# MotorBoardDev.net
KiCad netlist of a schematic drawn in EAGLE
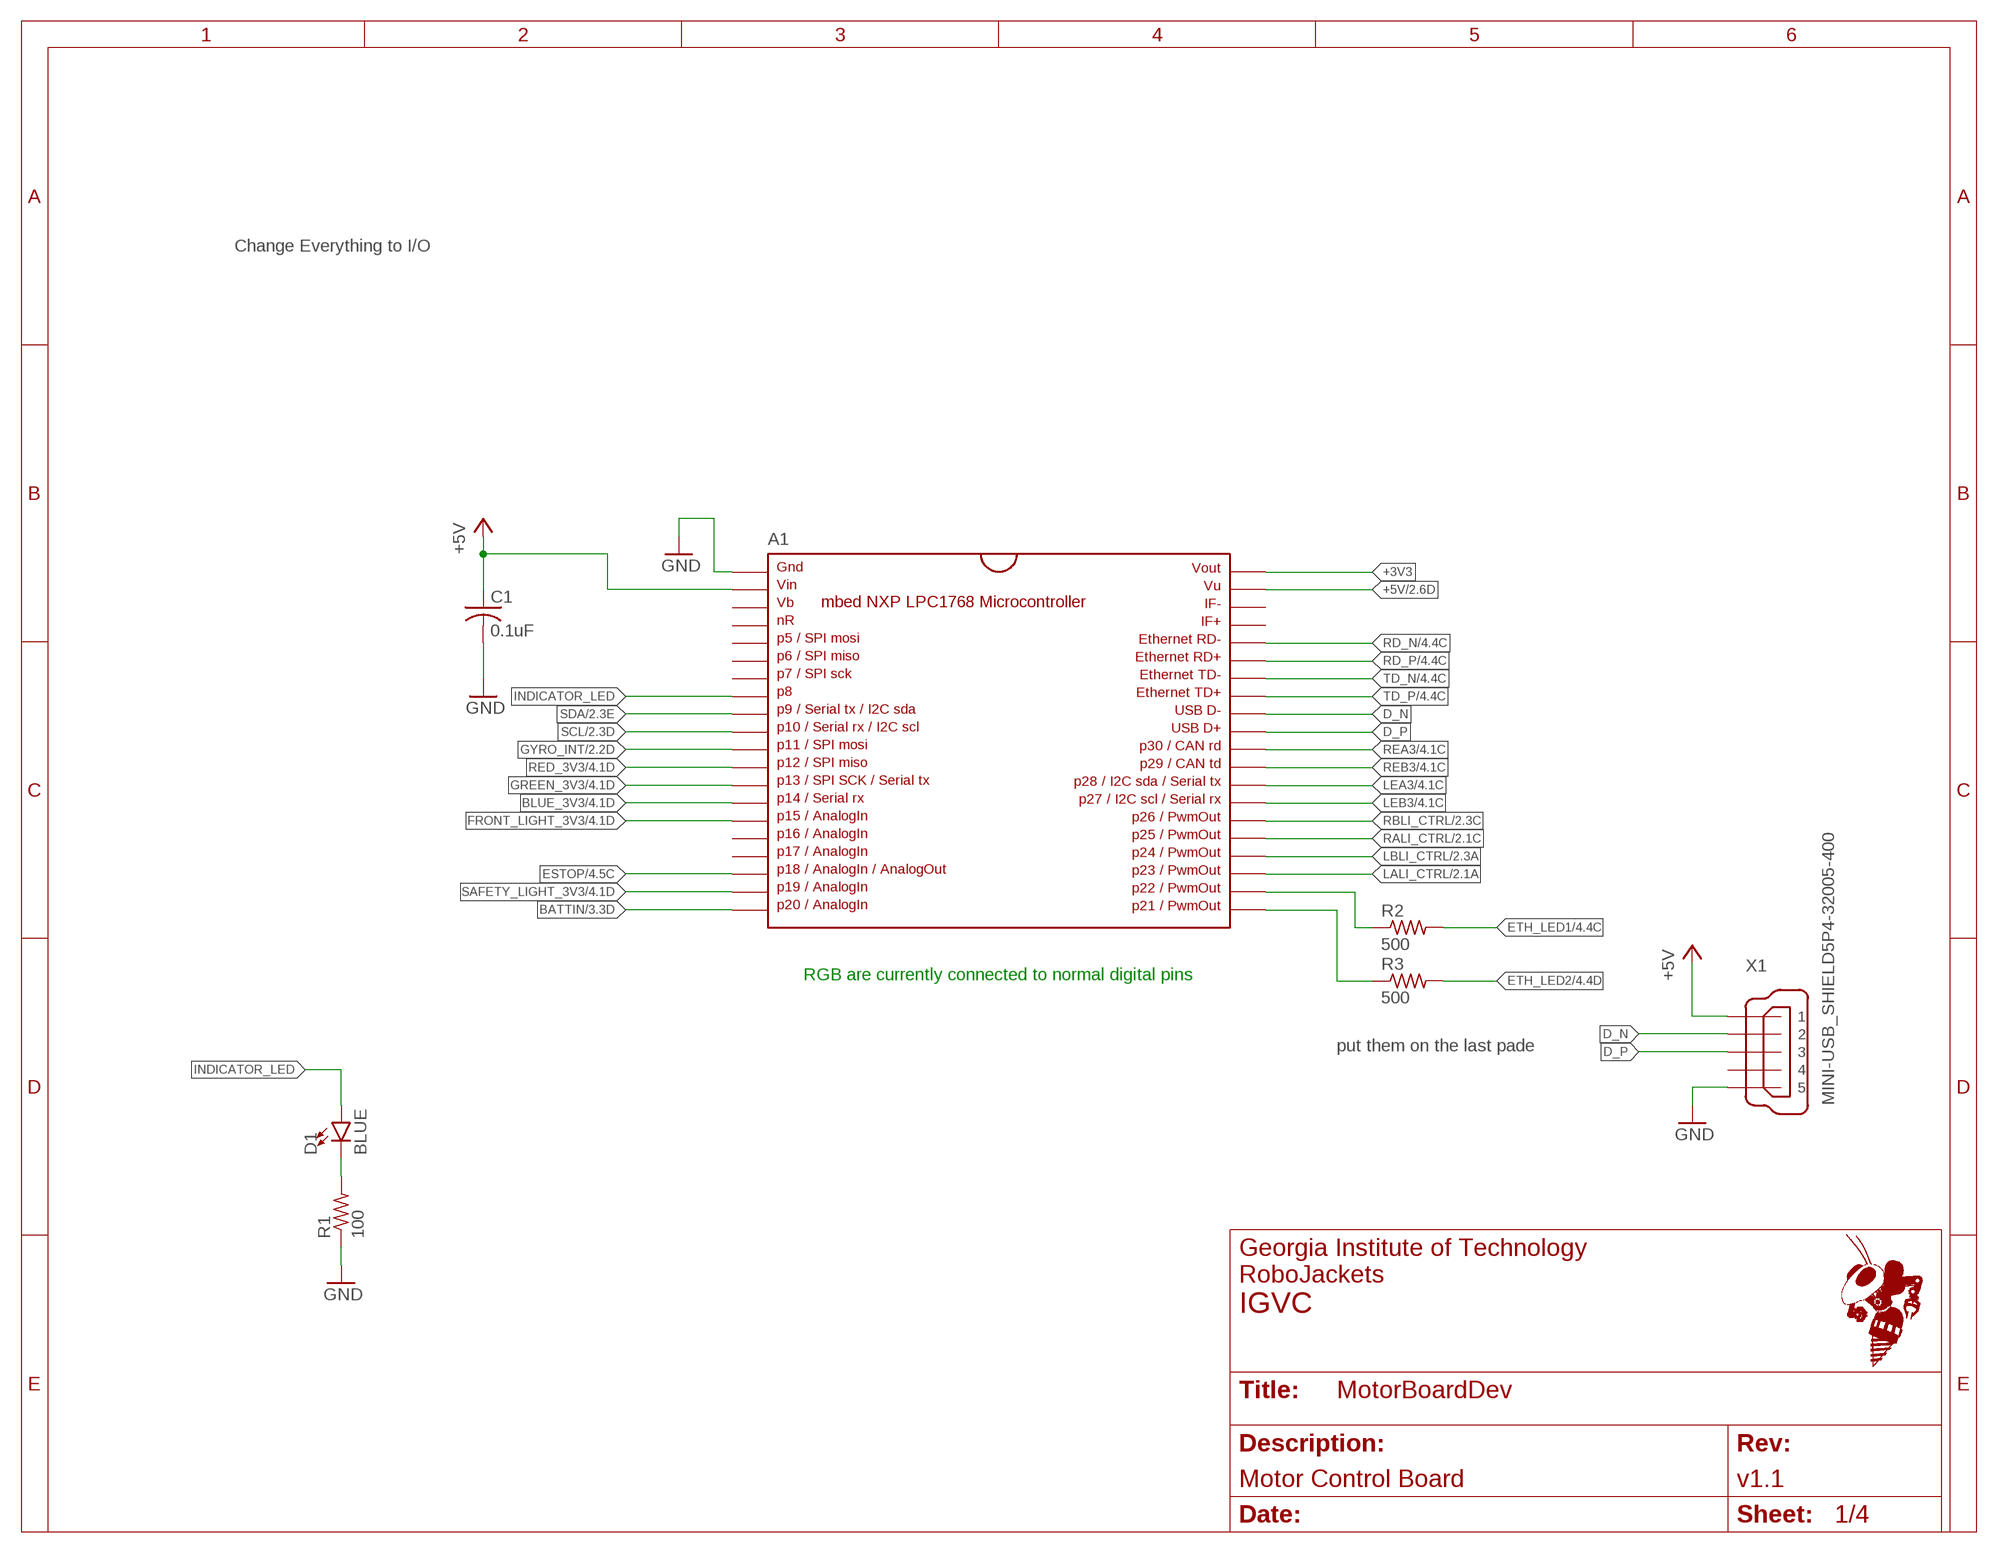
[diagram p0: schematic, sheet 1]
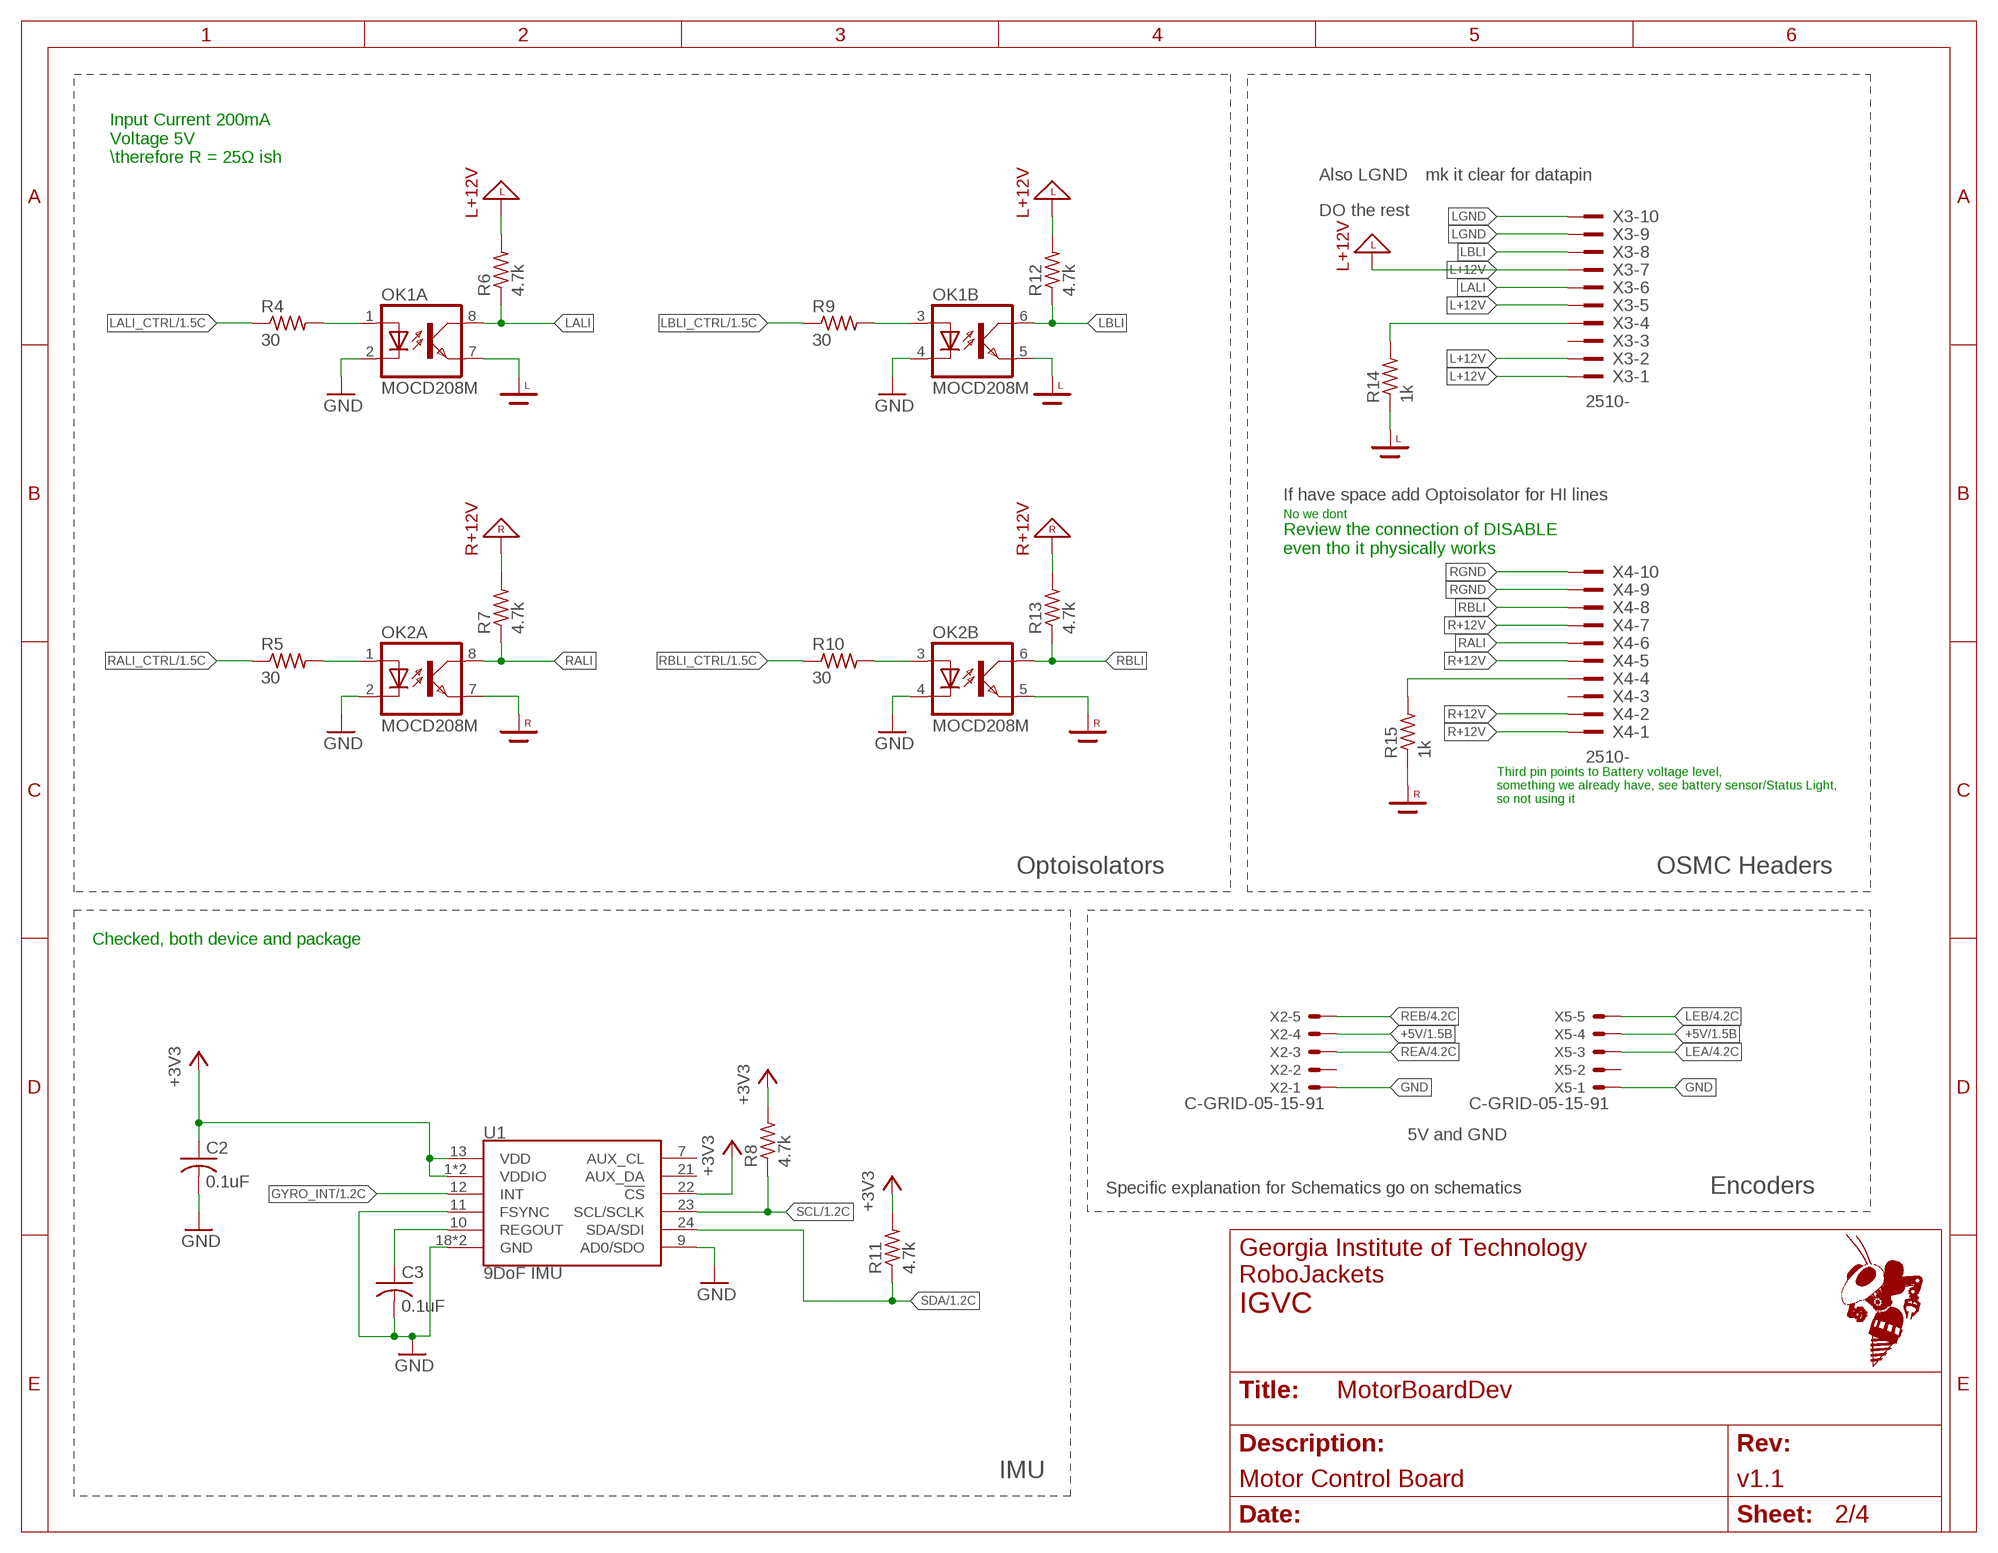
[diagram p1: schematic, sheet 2]
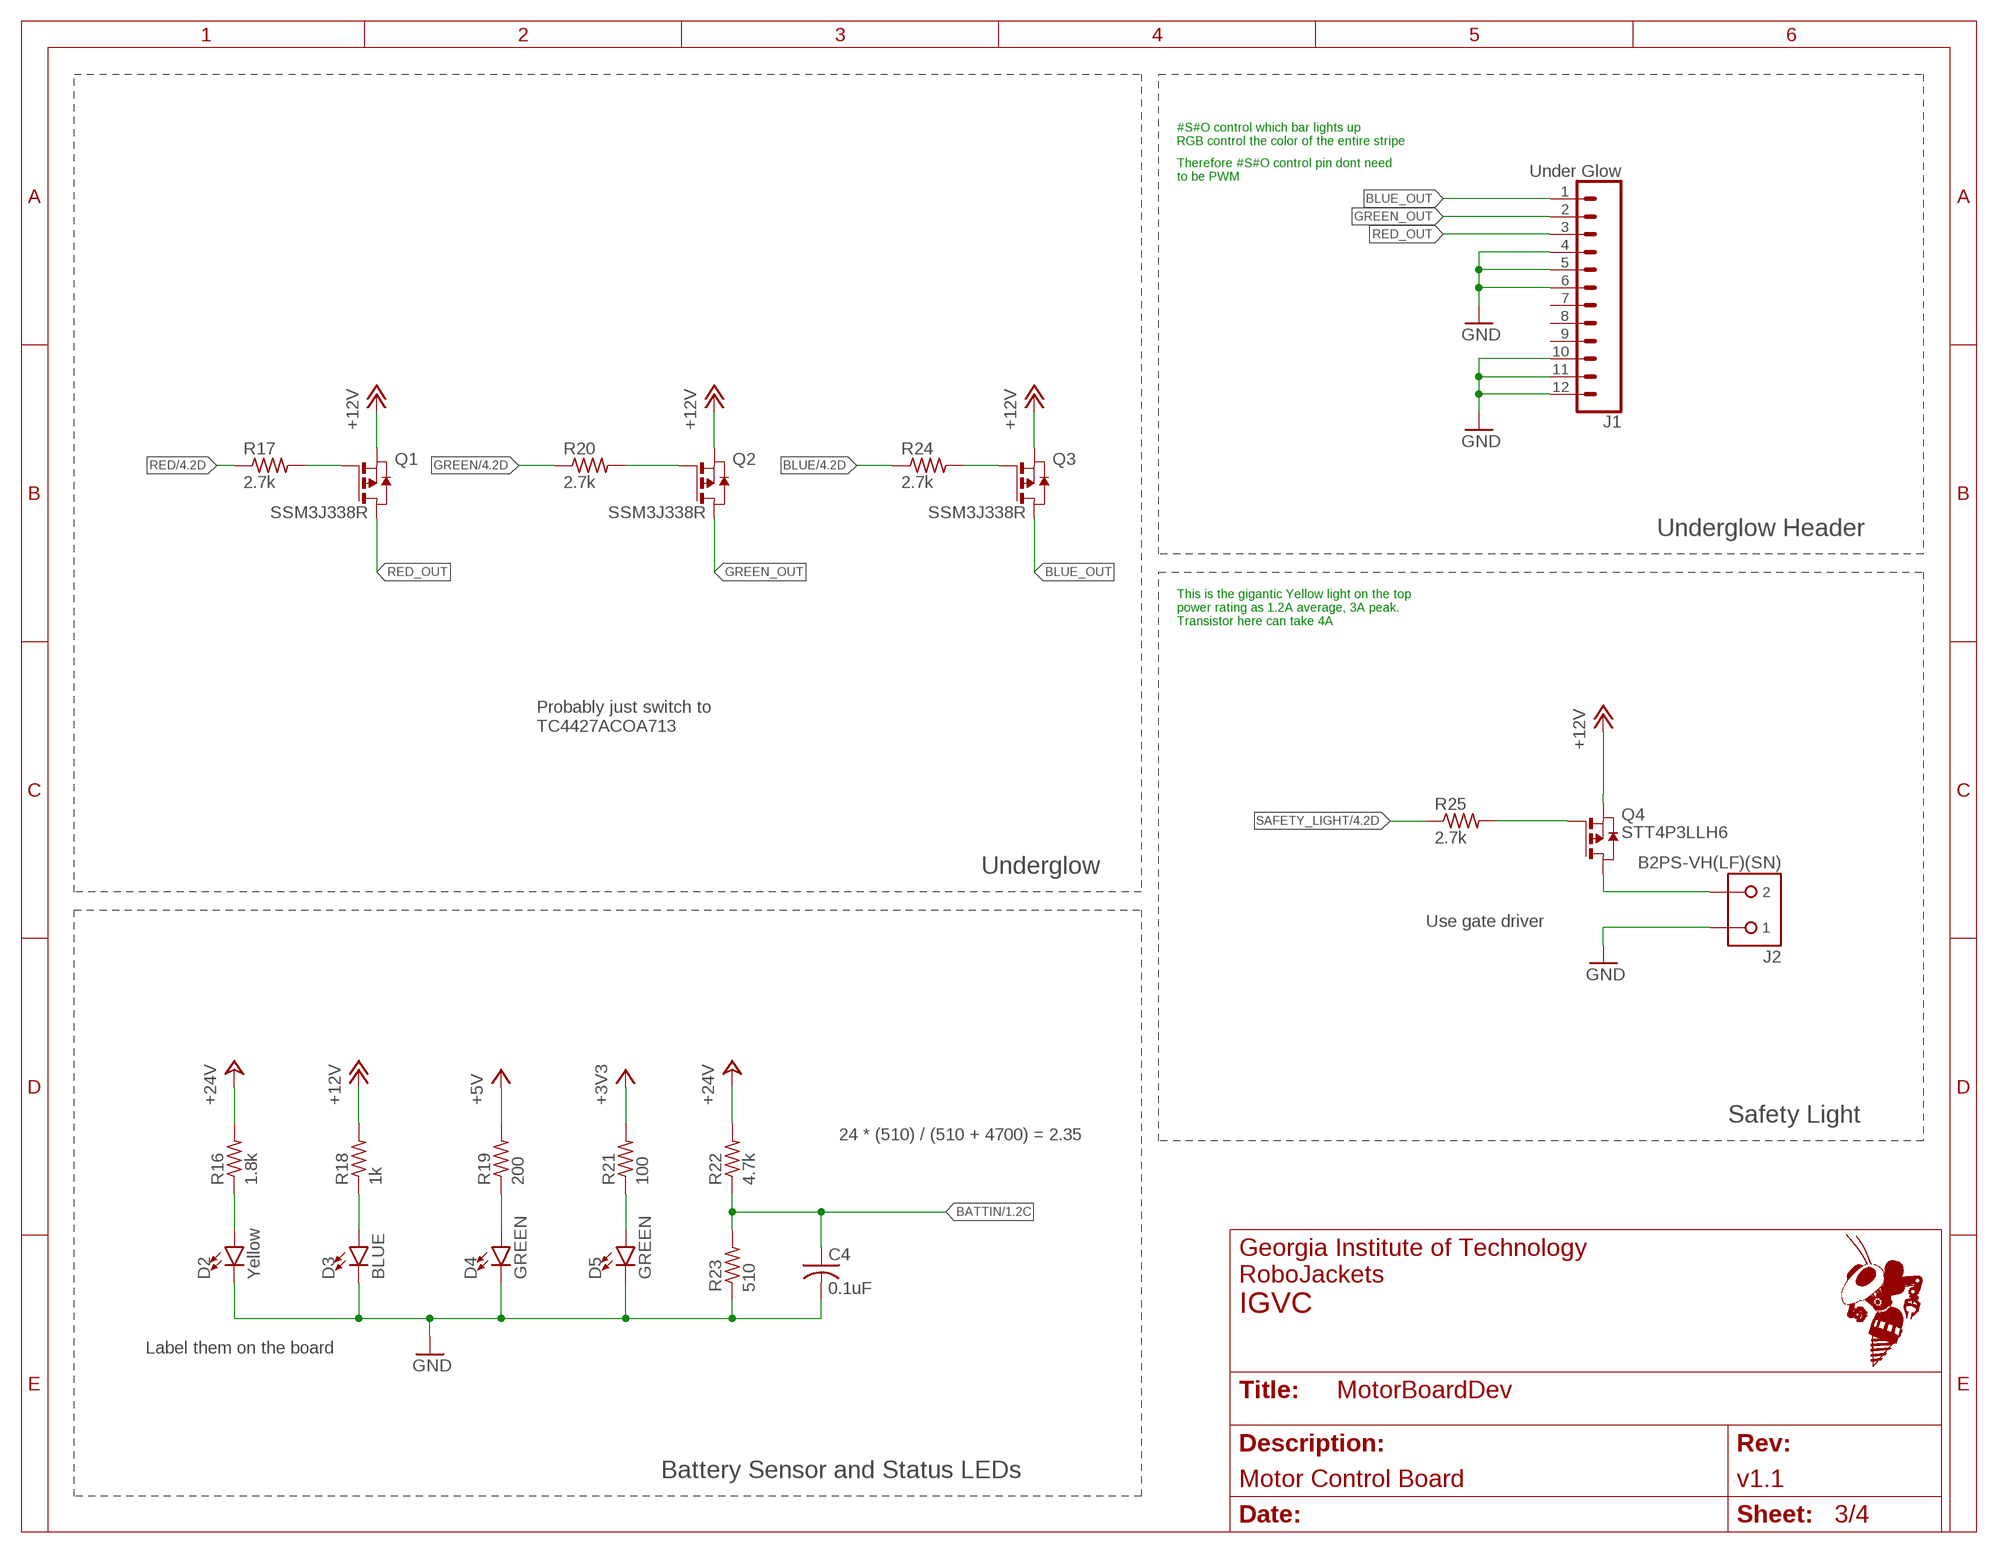
[diagram p2: schematic, sheet 3]
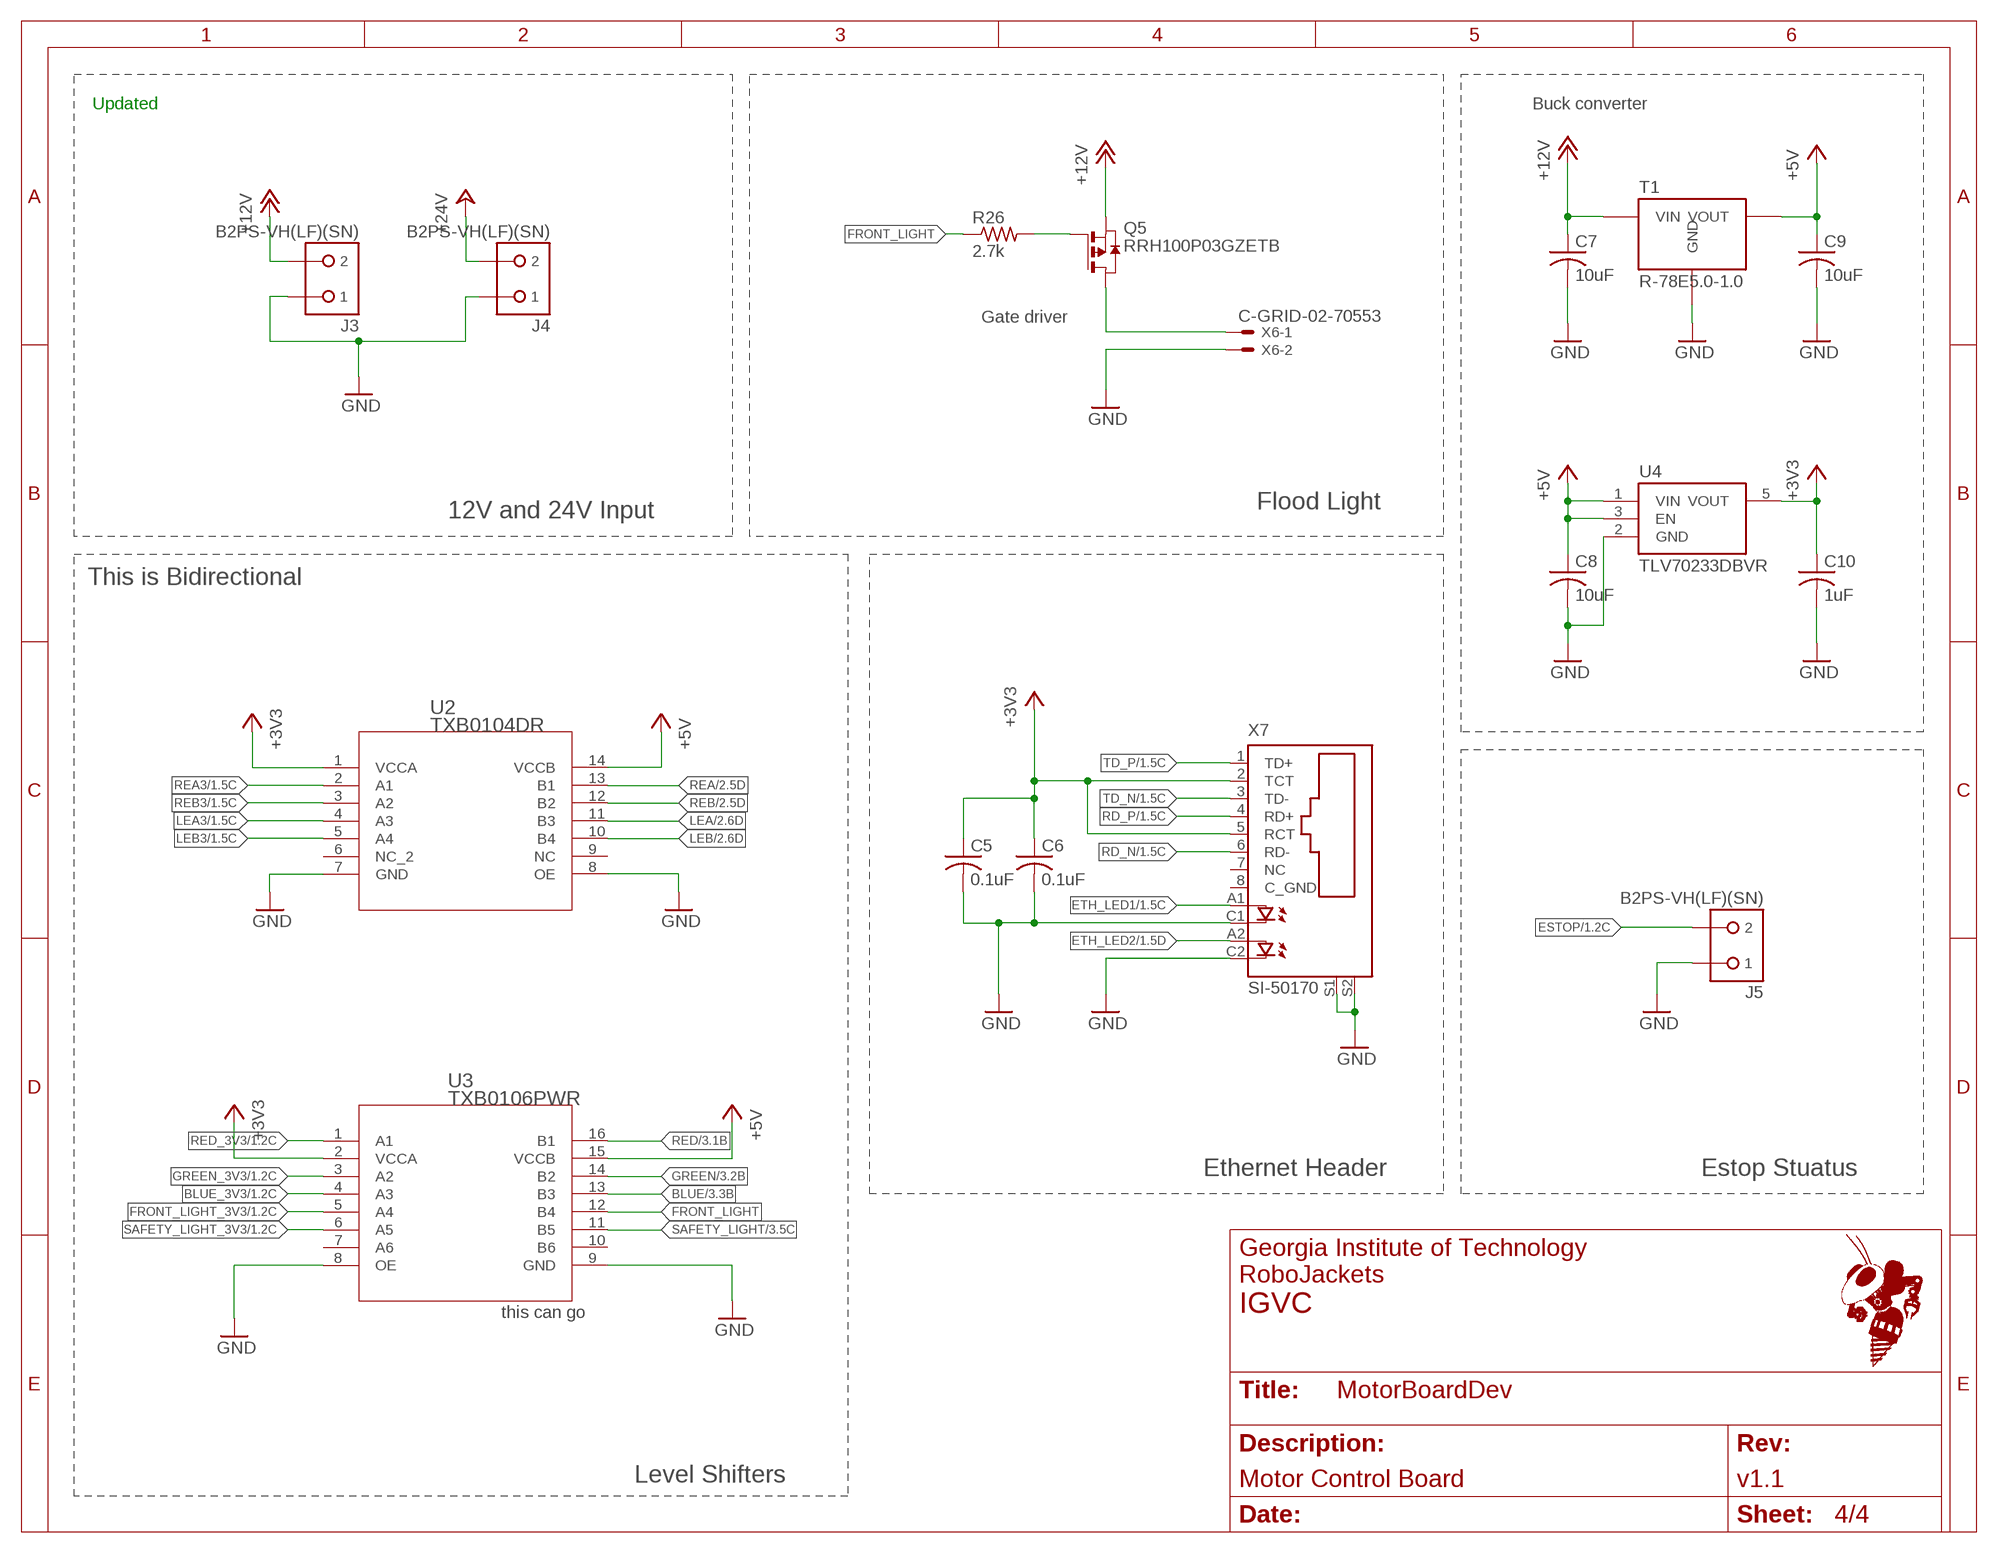
[diagram p3: schematic, sheet 4]

(export (version "E")
  (design (tool "Eeschema 10.0.6"))
  (components
    (comp (ref "C5")
      (value "0.1uF")
      (footprint "eagle-import:C0603")
      (libsource (lib "eagle-import") (part "C-USC0603"))
    )
    (comp (ref "C6")
      (value "0.1uF")
      (footprint "eagle-import:C0603")
      (libsource (lib "eagle-import") (part "C-USC0603"))
    )
    (comp (ref "C7")
      (value "10uF")
      (footprint "eagle-import:C0805")
      (libsource (lib "eagle-import") (part "C-USC0805"))
    )
    (comp (ref "C8")
      (value "10uF")
      (footprint "eagle-import:C0805")
      (libsource (lib "eagle-import") (part "C-USC0805"))
    )
    (comp (ref "C9")
      (value "10uF")
      (footprint "eagle-import:C0805")
      (libsource (lib "eagle-import") (part "C-USC0805"))
    )
    (comp (ref "C10")
      (value "1uF")
      (footprint "eagle-import:C0805")
      (libsource (lib "eagle-import") (part "C-USC0805"))
    )
    (comp (ref "J3")
      (value "B2PS-VH(LF)(SN)")
      (footprint "eagle-import:B2PS-CENTERED")
      (libsource (lib "eagle-import") (part "B2P?-VH(LF)(SN)S"))
    )
    (comp (ref "J4")
      (value "B2PS-VH(LF)(SN)")
      (footprint "eagle-import:B2PS-CENTERED")
      (libsource (lib "eagle-import") (part "B2P?-VH(LF)(SN)S"))
    )
    (comp (ref "J5")
      (value "B2PS-VH(LF)(SN)")
      (footprint "eagle-import:B2PS-CENTERED")
      (libsource (lib "eagle-import") (part "B2P?-VH(LF)(SN)S"))
    )
    (comp (ref "Q5")
      (value "RRH100P03GZETB")
      (footprint "eagle-import:SOIC-8")
      (libsource (lib "eagle-import") (part "RRH100P03GZETB"))
    )
    (comp (ref "R26")
      (value "2.7k")
      (footprint "eagle-import:R0603")
      (libsource (lib "eagle-import") (part "R-US_R0603"))
    )
    (comp (ref "T1")
      (value "R-78E5.0-1.0")
      (footprint "eagle-import:R-78E")
      (libsource (lib "eagle-import") (part "R-78E5.0-1.0"))
    )
    (comp (ref "U2")
      (value "TXB0104DR")
      (footprint "eagle-import:D14")
      (libsource (lib "eagle-import") (part "TXB0104DR"))
    )
    (comp (ref "U3")
      (value "TXB0106PWR")
      (footprint "eagle-import:PW16")
      (libsource (lib "eagle-import") (part "TXB0106PWR"))
    )
    (comp (ref "U4")
      (value "TLV70233DBVR")
      (footprint "eagle-import:SOT-23-5")
      (libsource (lib "eagle-import") (part "TLV70233DBVR"))
    )
    (comp (ref "X6")
      (value "C-GRID-02-70553")
      (footprint "eagle-import:70553-02")
      (libsource (lib "eagle-import") (part "C-GRID-02-70553"))
    )
    (comp (ref "X7")
      (value "SI-50170")
      (footprint "eagle-import:SI-50170")
      (libsource (lib "eagle-import") (part "SI-50170"))
    )
    (comp (ref "A1")
      (value "MBED1768")
      (footprint "eagle-import:SPARKFUN-BOARDS_DIL40_0.9")
      (libsource (lib "eagle-import") (part "SPARKFUN-BOARDS_MBED_NXP_LPC1768"))
    )
    (comp (ref "C1")
      (value "0.1uF")
      (footprint "eagle-import:C0603")
      (libsource (lib "eagle-import") (part "C-USC0603"))
    )
    (comp (ref "D1")
      (value "BLUE")
      (footprint "eagle-import:LED-0603")
      (libsource (lib "eagle-import") (part "LED-BLUE0603"))
    )
    (comp (ref "R1")
      (value "100")
      (footprint "eagle-import:R0603")
      (libsource (lib "eagle-import") (part "R-US_R0603"))
    )
    (comp (ref "R2")
      (value "500")
      (footprint "eagle-import:R0603")
      (libsource (lib "eagle-import") (part "R-US_R0603"))
    )
    (comp (ref "R3")
      (value "500")
      (footprint "eagle-import:R0603")
      (libsource (lib "eagle-import") (part "R-US_R0603"))
    )
    (comp (ref "X1")
      (value "MINI-USB_SHIELD5P4-32005-400")
      (footprint "eagle-import:32005-400")
      (libsource (lib "eagle-import") (part "MINI-USB_SHIELD5P4-32005-400"))
    )
    (comp (ref "C2")
      (value "0.1uF")
      (footprint "eagle-import:C0603")
      (libsource (lib "eagle-import") (part "C-USC0603"))
    )
    (comp (ref "C3")
      (value "0.1uF")
      (footprint "eagle-import:C0603")
      (libsource (lib "eagle-import") (part "C-USC0603"))
    )
    (comp (ref "OK1")
      (value "MOCD208M")
      (footprint "eagle-import:SOIC08-FAIRCHILD")
      (fields (field (name "MF") "FAIRCHILD SEMICONDUCTOR"))
      (libsource (lib "eagle-import") (part "MOCD20M8"))
    )
    (comp (ref "OK2")
      (value "MOCD208M")
      (footprint "eagle-import:SOIC08-FAIRCHILD")
      (fields (field (name "MF") "FAIRCHILD SEMICONDUCTOR"))
      (libsource (lib "eagle-import") (part "MOCD20M8"))
    )
    (comp (ref "R4")
      (value "30")
      (footprint "eagle-import:R0603")
      (libsource (lib "eagle-import") (part "R-US_R0603"))
    )
    (comp (ref "R5")
      (value "30")
      (footprint "eagle-import:R0603")
      (libsource (lib "eagle-import") (part "R-US_R0603"))
    )
    (comp (ref "R6")
      (value "4.7k")
      (footprint "eagle-import:R0603")
      (libsource (lib "eagle-import") (part "R-US_R0603"))
    )
    (comp (ref "R7")
      (value "4.7k")
      (footprint "eagle-import:R0603")
      (libsource (lib "eagle-import") (part "R-US_R0603"))
    )
    (comp (ref "R8")
      (value "4.7k")
      (footprint "eagle-import:R0603")
      (libsource (lib "eagle-import") (part "R-US_R0603"))
    )
    (comp (ref "R9")
      (value "30")
      (footprint "eagle-import:R0603")
      (libsource (lib "eagle-import") (part "R-US_R0603"))
    )
    (comp (ref "R10")
      (value "30")
      (footprint "eagle-import:R0603")
      (libsource (lib "eagle-import") (part "R-US_R0603"))
    )
    (comp (ref "R11")
      (value "4.7k")
      (footprint "eagle-import:R0603")
      (libsource (lib "eagle-import") (part "R-US_R0603"))
    )
    (comp (ref "R12")
      (value "4.7k")
      (footprint "eagle-import:R0603")
      (libsource (lib "eagle-import") (part "R-US_R0603"))
    )
    (comp (ref "R13")
      (value "4.7k")
      (footprint "eagle-import:R0603")
      (libsource (lib "eagle-import") (part "R-US_R0603"))
    )
    (comp (ref "R14")
      (value "1k")
      (footprint "eagle-import:R0603")
      (libsource (lib "eagle-import") (part "R-US_R0603"))
    )
    (comp (ref "R15")
      (value "1k")
      (footprint "eagle-import:R0603")
      (libsource (lib "eagle-import") (part "R-US_R0603"))
    )
    (comp (ref "U1")
      (value "9DoF IMU")
      (footprint "eagle-import:QFN24-3X3")
      (libsource (lib "eagle-import") (part "MPU-9250"))
    )
    (comp (ref "X2")
      (value "C-GRID-05-15-91")
      (footprint "eagle-import:15-91-05")
      (libsource (lib "eagle-import") (part "C-GRID-05-15-91"))
    )
    (comp (ref "X3")
      (value "2510-")
      (footprint "eagle-import:PAK100_2500-10")
      (fields (field (name "MF") "3M") (field (name "MPN") "2510-6002UB"))
      (libsource (lib "eagle-import") (part "2510-"))
    )
    (comp (ref "X4")
      (value "2510-")
      (footprint "eagle-import:PAK100_2500-10")
      (fields (field (name "MF") "3M") (field (name "MPN") "2510-6002UB"))
      (libsource (lib "eagle-import") (part "2510-"))
    )
    (comp (ref "X5")
      (value "C-GRID-05-15-91")
      (footprint "eagle-import:15-91-05")
      (libsource (lib "eagle-import") (part "C-GRID-05-15-91"))
    )
    (comp (ref "C4")
      (value "0.1uF")
      (footprint "eagle-import:C0603")
      (libsource (lib "eagle-import") (part "C-USC0603"))
    )
    (comp (ref "D2")
      (value "Yellow")
      (footprint "eagle-import:LED-0603")
      (libsource (lib "eagle-import") (part "LED-YELLOW0603"))
    )
    (comp (ref "D3")
      (value "BLUE")
      (footprint "eagle-import:LED-0603")
      (libsource (lib "eagle-import") (part "LED-BLUE0603"))
    )
    (comp (ref "D4")
      (value "GREEN")
      (footprint "eagle-import:LED-0603")
      (libsource (lib "eagle-import") (part "LED-GREEN0603"))
    )
    (comp (ref "D5")
      (value "GREEN")
      (footprint "eagle-import:LED-0603")
      (libsource (lib "eagle-import") (part "LED-GREEN0603"))
    )
    (comp (ref "J1")
      (value "Under Glow")
      (footprint "eagle-import:1X12_LOCK_LONGPADS")
      (libsource (lib "eagle-import") (part "CONN_12LOCK_LONGPADS"))
    )
    (comp (ref "J2")
      (value "B2PS-VH(LF)(SN)")
      (footprint "eagle-import:B2PS-CENTERED")
      (libsource (lib "eagle-import") (part "B2P?-VH(LF)(SN)S"))
    )
    (comp (ref "Q1")
      (value "SSM3J338R")
      (footprint "eagle-import:SOT-23-3")
      (libsource (lib "eagle-import") (part "PMOS"))
    )
    (comp (ref "Q2")
      (value "SSM3J338R")
      (footprint "eagle-import:SOT-23-3")
      (libsource (lib "eagle-import") (part "PMOS"))
    )
    (comp (ref "Q3")
      (value "SSM3J338R")
      (footprint "eagle-import:SOT-23-3")
      (libsource (lib "eagle-import") (part "PMOS"))
    )
    (comp (ref "Q4")
      (value "STT4P3LLH6")
      (footprint "eagle-import:SOT23-6")
      (libsource (lib "eagle-import") (part "STT4P3LLH6"))
    )
    (comp (ref "R16")
      (value "1.8k")
      (footprint "eagle-import:R0603")
      (libsource (lib "eagle-import") (part "R-US_R0603"))
    )
    (comp (ref "R17")
      (value "2.7k")
      (footprint "eagle-import:R0603")
      (libsource (lib "eagle-import") (part "R-US_R0603"))
    )
    (comp (ref "R18")
      (value "1k")
      (footprint "eagle-import:R0603")
      (libsource (lib "eagle-import") (part "R-US_R0603"))
    )
    (comp (ref "R19")
      (value "200")
      (footprint "eagle-import:R0603")
      (libsource (lib "eagle-import") (part "R-US_R0603"))
    )
    (comp (ref "R20")
      (value "2.7k")
      (footprint "eagle-import:R0603")
      (libsource (lib "eagle-import") (part "R-US_R0603"))
    )
    (comp (ref "R21")
      (value "100")
      (footprint "eagle-import:R0603")
      (libsource (lib "eagle-import") (part "R-US_R0603"))
    )
    (comp (ref "R22")
      (value "4.7k")
      (footprint "eagle-import:R0603")
      (libsource (lib "eagle-import") (part "R-US_R0603"))
    )
    (comp (ref "R23")
      (value "510")
      (footprint "eagle-import:R0603")
      (libsource (lib "eagle-import") (part "R-US_R0603"))
    )
    (comp (ref "R24")
      (value "2.7k")
      (footprint "eagle-import:R0603")
      (libsource (lib "eagle-import") (part "R-US_R0603"))
    )
    (comp (ref "R25")
      (value "2.7k")
      (footprint "eagle-import:R0603")
      (libsource (lib "eagle-import") (part "R-US_R0603"))
    )
  )
  (nets
    (net (code "1") (name "+3V3") (class "Default")
      (node (ref "A1") (pin "40") (pinfunction "P$40_40") (pintype "bidirectional"))
      (node (ref "C10") (pin "1") (pinfunction "1_1") (pintype "passive"))
      (node (ref "C2") (pin "1") (pinfunction "1_1") (pintype "passive"))
      (node (ref "C5") (pin "1") (pinfunction "1_1") (pintype "passive"))
      (node (ref "C6") (pin "1") (pinfunction "1_1") (pintype "passive"))
      (node (ref "R11") (pin "2") (pinfunction "2_2") (pintype "passive"))
      (node (ref "R21") (pin "2") (pinfunction "2_2") (pintype "passive"))
      (node (ref "R8") (pin "2") (pinfunction "2_2") (pintype "passive"))
      (node (ref "U1") (pin "1") (pinfunction "VDDIO_1") (pintype "bidirectional"))
      (node (ref "U1") (pin "13") (pinfunction "VDD_13") (pintype "bidirectional"))
      (node (ref "U1") (pin "22") (pinfunction "~{CS}_22") (pintype "bidirectional"))
      (node (ref "U1") (pin "8") (pinfunction "VDDIO_8") (pintype "bidirectional"))
      (node (ref "U2") (pin "1") (pinfunction "VCCA_1") (pintype "power_in"))
      (node (ref "U3") (pin "2") (pinfunction "VCCA_2") (pintype "power_in"))
      (node (ref "U4") (pin "5") (pinfunction "VOUT_5") (pintype "bidirectional"))
      (node (ref "X7") (pin "2") (pinfunction "TCT_2") (pintype "passive"))
      (node (ref "X7") (pin "5") (pinfunction "RCT_5") (pintype "passive"))
    )
    (net (code "2") (name "+5V") (class "Default")
      (node (ref "A1") (pin "2") (pinfunction "P$2_2") (pintype "bidirectional"))
      (node (ref "A1") (pin "39") (pinfunction "P$39_39") (pintype "bidirectional"))
      (node (ref "C1") (pin "1") (pinfunction "1_1") (pintype "passive"))
      (node (ref "C8") (pin "1") (pinfunction "1_1") (pintype "passive"))
      (node (ref "C9") (pin "1") (pinfunction "1_1") (pintype "passive"))
      (node (ref "R19") (pin "2") (pinfunction "2_2") (pintype "passive"))
      (node (ref "T1") (pin "3") (pinfunction "VOUT_3") (pintype "bidirectional"))
      (node (ref "U2") (pin "14") (pinfunction "VCCB_14") (pintype "power_in"))
      (node (ref "U3") (pin "15") (pinfunction "VCCB_15") (pintype "power_in"))
      (node (ref "U4") (pin "1") (pinfunction "VIN_1") (pintype "bidirectional"))
      (node (ref "U4") (pin "3") (pinfunction "EN_3") (pintype "bidirectional"))
      (node (ref "X1") (pin "1") (pinfunction "1_1") (pintype "passive"))
      (node (ref "X2") (pin "4") (pinfunction "S_4") (pintype "passive"))
      (node (ref "X5") (pin "4") (pinfunction "S_4") (pintype "passive"))
    )
    (net (code "3") (name "+12V") (class "Default")
      (node (ref "C7") (pin "1") (pinfunction "1_1") (pintype "passive"))
      (node (ref "J3") (pin "2") (pinfunction "2_2") (pintype "bidirectional"))
      (node (ref "Q1") (pin "2") (pinfunction "S_2") (pintype "passive"))
      (node (ref "Q2") (pin "2") (pinfunction "S_2") (pintype "passive"))
      (node (ref "Q3") (pin "2") (pinfunction "S_2") (pintype "passive"))
      (node (ref "Q4") (pin "4") (pinfunction "S_4") (pintype "passive"))
      (node (ref "Q5") (pin "1") (pinfunction "S_1") (pintype "passive"))
      (node (ref "Q5") (pin "2") (pinfunction "S_2") (pintype "passive"))
      (node (ref "Q5") (pin "3") (pinfunction "S_3") (pintype "passive"))
      (node (ref "R18") (pin "2") (pinfunction "2_2") (pintype "passive"))
      (node (ref "T1") (pin "1") (pinfunction "VIN_1") (pintype "bidirectional"))
    )
    (net (code "4") (name "+24V") (class "Default")
      (node (ref "J4") (pin "2") (pinfunction "2_2") (pintype "bidirectional"))
      (node (ref "R16") (pin "2") (pinfunction "2_2") (pintype "passive"))
      (node (ref "R22") (pin "2") (pinfunction "2_2") (pintype "passive"))
    )
    (net (code "5") (name "BATTIN") (class "Default")
      (node (ref "A1") (pin "20") (pinfunction "P$20_20") (pintype "bidirectional"))
      (node (ref "C4") (pin "1") (pinfunction "1_1") (pintype "passive"))
      (node (ref "R22") (pin "1") (pinfunction "1_1") (pintype "passive"))
      (node (ref "R23") (pin "2") (pinfunction "2_2") (pintype "passive"))
    )
    (net (code "6") (name "BLUE") (class "Default")
      (node (ref "R24") (pin "1") (pinfunction "1_1") (pintype "passive"))
      (node (ref "U3") (pin "13") (pinfunction "B3_13") (pintype "bidirectional"))
    )
    (net (code "7") (name "BLUE_3V3") (class "Default")
      (node (ref "A1") (pin "14") (pinfunction "P$14_14") (pintype "bidirectional"))
      (node (ref "U3") (pin "4") (pinfunction "A3_4") (pintype "bidirectional"))
    )
    (net (code "8") (name "BLUE_OUT") (class "Default")
      (node (ref "J1") (pin "1") (pinfunction "1_1") (pintype "passive"))
      (node (ref "Q3") (pin "3") (pinfunction "D_3") (pintype "passive"))
    )
    (net (code "9") (name "D_N") (class "Default")
      (node (ref "A1") (pin "32") (pinfunction "P$32_32") (pintype "bidirectional"))
      (node (ref "X1") (pin "2") (pinfunction "2_2") (pintype "passive"))
    )
    (net (code "10") (name "D_P") (class "Default")
      (node (ref "A1") (pin "31") (pinfunction "P$31_31") (pintype "bidirectional"))
      (node (ref "X1") (pin "3") (pinfunction "3_3") (pintype "passive"))
    )
    (net (code "11") (name "ESTOP") (class "Default")
      (node (ref "A1") (pin "18") (pinfunction "P$18_18") (pintype "bidirectional"))
      (node (ref "J5") (pin "2") (pinfunction "2_2") (pintype "bidirectional"))
    )
    (net (code "12") (name "ETH_LED1") (class "Default")
      (node (ref "R2") (pin "2") (pinfunction "2_2") (pintype "passive"))
      (node (ref "X7") (pin "A1") (pinfunction "A_A1") (pintype "passive"))
    )
    (net (code "13") (name "ETH_LED2") (class "Default")
      (node (ref "R3") (pin "2") (pinfunction "2_2") (pintype "passive"))
      (node (ref "X7") (pin "A2") (pinfunction "A1_A2") (pintype "passive"))
    )
    (net (code "14") (name "FRONT_LIGHT") (class "Default")
      (node (ref "R26") (pin "1") (pinfunction "1_1") (pintype "passive"))
      (node (ref "U3") (pin "12") (pinfunction "B4_12") (pintype "bidirectional"))
    )
    (net (code "15") (name "FRONT_LIGHT_3V3") (class "Default")
      (node (ref "A1") (pin "15") (pinfunction "P$15_15") (pintype "bidirectional"))
      (node (ref "U3") (pin "5") (pinfunction "A4_5") (pintype "bidirectional"))
    )
    (net (code "16") (name "GND") (class "Default")
      (node (ref "A1") (pin "1") (pinfunction "P$1_1") (pintype "bidirectional"))
      (node (ref "C1") (pin "2") (pinfunction "2_2") (pintype "passive"))
      (node (ref "C10") (pin "2") (pinfunction "2_2") (pintype "passive"))
      (node (ref "C2") (pin "2") (pinfunction "2_2") (pintype "passive"))
      (node (ref "C3") (pin "2") (pinfunction "2_2") (pintype "passive"))
      (node (ref "C4") (pin "2") (pinfunction "2_2") (pintype "passive"))
      (node (ref "C5") (pin "2") (pinfunction "2_2") (pintype "passive"))
      (node (ref "C6") (pin "2") (pinfunction "2_2") (pintype "passive"))
      (node (ref "C7") (pin "2") (pinfunction "2_2") (pintype "passive"))
      (node (ref "C8") (pin "2") (pinfunction "2_2") (pintype "passive"))
      (node (ref "C9") (pin "2") (pinfunction "2_2") (pintype "passive"))
      (node (ref "D2") (pin "C") (pinfunction "C_C") (pintype "passive"))
      (node (ref "D3") (pin "C") (pinfunction "C_C") (pintype "passive"))
      (node (ref "D4") (pin "C") (pinfunction "C_C") (pintype "passive"))
      (node (ref "D5") (pin "C") (pinfunction "C_C") (pintype "passive"))
      (node (ref "J1") (pin "10") (pinfunction "10_10") (pintype "passive"))
      (node (ref "J1") (pin "11") (pinfunction "11_11") (pintype "passive"))
      (node (ref "J1") (pin "12") (pinfunction "12_12") (pintype "passive"))
      (node (ref "J1") (pin "4") (pinfunction "4_4") (pintype "passive"))
      (node (ref "J1") (pin "5") (pinfunction "5_5") (pintype "passive"))
      (node (ref "J1") (pin "6") (pinfunction "6_6") (pintype "passive"))
      (node (ref "J2") (pin "1") (pinfunction "1_1") (pintype "bidirectional"))
      (node (ref "J3") (pin "1") (pinfunction "1_1") (pintype "bidirectional"))
      (node (ref "J4") (pin "1") (pinfunction "1_1") (pintype "bidirectional"))
      (node (ref "J5") (pin "1") (pinfunction "1_1") (pintype "bidirectional"))
      (node (ref "OK1") (pin "2") (pinfunction "C_2") (pintype "passive"))
      (node (ref "OK1") (pin "4") (pinfunction "C_4") (pintype "passive"))
      (node (ref "OK2") (pin "2") (pinfunction "C_2") (pintype "passive"))
      (node (ref "OK2") (pin "4") (pinfunction "C_4") (pintype "passive"))
      (node (ref "R1") (pin "1") (pinfunction "1_1") (pintype "passive"))
      (node (ref "R23") (pin "1") (pinfunction "1_1") (pintype "passive"))
      (node (ref "T1") (pin "2") (pinfunction "GND_2") (pintype "bidirectional"))
      (node (ref "U1") (pin "11") (pinfunction "FSYNC_11") (pintype "bidirectional"))
      (node (ref "U1") (pin "18") (pinfunction "GND_18") (pintype "bidirectional"))
      (node (ref "U1") (pin "20") (pinfunction "GND_20") (pintype "bidirectional"))
      (node (ref "U1") (pin "9") (pinfunction "AD0/SDO_9") (pintype "bidirectional"))
      (node (ref "U2") (pin "7") (pinfunction "GND_7") (pintype "power_in"))
      (node (ref "U2") (pin "8") (pinfunction "OE_8") (pintype "output"))
      (node (ref "U3") (pin "8") (pinfunction "OE_8") (pintype "output"))
      (node (ref "U3") (pin "9") (pinfunction "GND_9") (pintype "power_in"))
      (node (ref "U4") (pin "2") (pinfunction "GND_2") (pintype "bidirectional"))
      (node (ref "X1") (pin "5") (pinfunction "5_5") (pintype "passive"))
      (node (ref "X2") (pin "1") (pinfunction "S_1") (pintype "passive"))
      (node (ref "X5") (pin "1") (pinfunction "S_1") (pintype "passive"))
      (node (ref "X6") (pin "2") (pinfunction "S_2") (pintype "passive"))
      (node (ref "X7") (pin "C1") (pinfunction "C_C1") (pintype "passive"))
      (node (ref "X7") (pin "C2") (pinfunction "C1_C2") (pintype "passive"))
      (node (ref "X7") (pin "S1") (pinfunction "S1_S1") (pintype "passive"))
      (node (ref "X7") (pin "S2") (pinfunction "S2_S2") (pintype "passive"))
    )
    (net (code "17") (name "GREEN") (class "Default")
      (node (ref "R20") (pin "1") (pinfunction "1_1") (pintype "passive"))
      (node (ref "U3") (pin "14") (pinfunction "B2_14") (pintype "bidirectional"))
    )
    (net (code "18") (name "GREEN_3V3") (class "Default")
      (node (ref "A1") (pin "13") (pinfunction "P$13_13") (pintype "bidirectional"))
      (node (ref "U3") (pin "3") (pinfunction "A2_3") (pintype "bidirectional"))
    )
    (net (code "19") (name "GREEN_OUT") (class "Default")
      (node (ref "J1") (pin "2") (pinfunction "2_2") (pintype "passive"))
      (node (ref "Q2") (pin "3") (pinfunction "D_3") (pintype "passive"))
    )
    (net (code "20") (name "GYRO_INT") (class "Default")
      (node (ref "A1") (pin "11") (pinfunction "P$11_11") (pintype "bidirectional"))
      (node (ref "U1") (pin "12") (pinfunction "INT_12") (pintype "bidirectional"))
    )
    (net (code "21") (name "INDICATOR_LED") (class "Default")
      (node (ref "A1") (pin "8") (pinfunction "P$8_8") (pintype "bidirectional"))
      (node (ref "D1") (pin "A") (pinfunction "A_A") (pintype "passive"))
    )
    (net (code "22") (name "L+12V") (class "Default")
      (node (ref "R12") (pin "2") (pinfunction "2_2") (pintype "passive"))
      (node (ref "R6") (pin "2") (pinfunction "2_2") (pintype "passive"))
      (node (ref "X3") (pin "1") (pinfunction "KL_1") (pintype "passive"))
      (node (ref "X3") (pin "2") (pinfunction "KL_2") (pintype "passive"))
      (node (ref "X3") (pin "5") (pinfunction "KL_5") (pintype "passive"))
      (node (ref "X3") (pin "7") (pinfunction "KL_7") (pintype "passive"))
    )
    (net (code "23") (name "LALI") (class "Default")
      (node (ref "OK1") (pin "8") (pinfunction "COL_8") (pintype "passive"))
      (node (ref "R6") (pin "1") (pinfunction "1_1") (pintype "passive"))
      (node (ref "X3") (pin "6") (pinfunction "KL_6") (pintype "passive"))
    )
    (net (code "24") (name "LALI_CTRL") (class "Default")
      (node (ref "A1") (pin "23") (pinfunction "P$23_23") (pintype "bidirectional"))
      (node (ref "R4") (pin "1") (pinfunction "1_1") (pintype "passive"))
    )
    (net (code "25") (name "LBLI") (class "Default")
      (node (ref "OK1") (pin "6") (pinfunction "COL_6") (pintype "passive"))
      (node (ref "R12") (pin "1") (pinfunction "1_1") (pintype "passive"))
      (node (ref "X3") (pin "8") (pinfunction "KL_8") (pintype "passive"))
    )
    (net (code "26") (name "LBLI_CTRL") (class "Default")
      (node (ref "A1") (pin "24") (pinfunction "P$24_24") (pintype "bidirectional"))
      (node (ref "R9") (pin "1") (pinfunction "1_1") (pintype "passive"))
    )
    (net (code "27") (name "LEA") (class "Default")
      (node (ref "U2") (pin "11") (pinfunction "B3_11") (pintype "bidirectional"))
      (node (ref "X5") (pin "3") (pinfunction "S_3") (pintype "passive"))
    )
    (net (code "28") (name "LEA3") (class "Default")
      (node (ref "A1") (pin "28") (pinfunction "P$28_28") (pintype "bidirectional"))
      (node (ref "U2") (pin "4") (pinfunction "A3_4") (pintype "bidirectional"))
    )
    (net (code "29") (name "LEB") (class "Default")
      (node (ref "U2") (pin "10") (pinfunction "B4_10") (pintype "bidirectional"))
      (node (ref "X5") (pin "5") (pinfunction "S_5") (pintype "passive"))
    )
    (net (code "30") (name "LEB3") (class "Default")
      (node (ref "A1") (pin "27") (pinfunction "P$27_27") (pintype "bidirectional"))
      (node (ref "U2") (pin "5") (pinfunction "A4_5") (pintype "bidirectional"))
    )
    (net (code "31") (name "LGND") (class "Default")
      (node (ref "OK1") (pin "5") (pinfunction "EMIT_5") (pintype "passive"))
      (node (ref "OK1") (pin "7") (pinfunction "EMIT_7") (pintype "passive"))
      (node (ref "R14") (pin "1") (pinfunction "1_1") (pintype "passive"))
      (node (ref "X3") (pin "10") (pinfunction "KL_10") (pintype "passive"))
      (node (ref "X3") (pin "9") (pinfunction "KL_9") (pintype "passive"))
    )
    (net (code "32") (name "Net-(A1-P$21)") (class "Default")
      (node (ref "A1") (pin "21") (pinfunction "P$21_21") (pintype "bidirectional"))
      (node (ref "R3") (pin "1") (pinfunction "1_1") (pintype "passive"))
    )
    (net (code "33") (name "Net-(A1-P$22)") (class "Default")
      (node (ref "A1") (pin "22") (pinfunction "P$22_22") (pintype "bidirectional"))
      (node (ref "R2") (pin "1") (pinfunction "1_1") (pintype "passive"))
    )
    (net (code "34") (name "Net-(D1-PadC)") (class "Default")
      (node (ref "D1") (pin "C") (pinfunction "C_C") (pintype "passive"))
      (node (ref "R1") (pin "2") (pinfunction "2_2") (pintype "passive"))
    )
    (net (code "35") (name "Net-(D2-PadA)") (class "Default")
      (node (ref "D2") (pin "A") (pinfunction "A_A") (pintype "passive"))
      (node (ref "R16") (pin "1") (pinfunction "1_1") (pintype "passive"))
    )
    (net (code "36") (name "Net-(D3-PadA)") (class "Default")
      (node (ref "D3") (pin "A") (pinfunction "A_A") (pintype "passive"))
      (node (ref "R18") (pin "1") (pinfunction "1_1") (pintype "passive"))
    )
    (net (code "37") (name "Net-(D4-PadA)") (class "Default")
      (node (ref "D4") (pin "A") (pinfunction "A_A") (pintype "passive"))
      (node (ref "R19") (pin "1") (pinfunction "1_1") (pintype "passive"))
    )
    (net (code "38") (name "Net-(D5-PadA)") (class "Default")
      (node (ref "D5") (pin "A") (pinfunction "A_A") (pintype "passive"))
      (node (ref "R21") (pin "1") (pinfunction "1_1") (pintype "passive"))
    )
    (net (code "39") (name "Net-(J2-Pad2)") (class "Default")
      (node (ref "J2") (pin "2") (pinfunction "2_2") (pintype "bidirectional"))
      (node (ref "Q4") (pin "1") (pinfunction "D_1") (pintype "passive"))
      (node (ref "Q4") (pin "2") (pinfunction "D_2") (pintype "passive"))
      (node (ref "Q4") (pin "5") (pinfunction "D_5") (pintype "passive"))
      (node (ref "Q4") (pin "6") (pinfunction "D_6") (pintype "passive"))
    )
    (net (code "40") (name "Net-(OK1A-A)") (class "Default")
      (node (ref "OK1") (pin "1") (pinfunction "A_1") (pintype "passive"))
      (node (ref "R4") (pin "2") (pinfunction "2_2") (pintype "passive"))
    )
    (net (code "41") (name "Net-(OK1B-A)") (class "Default")
      (node (ref "OK1") (pin "3") (pinfunction "A_3") (pintype "passive"))
      (node (ref "R9") (pin "2") (pinfunction "2_2") (pintype "passive"))
    )
    (net (code "42") (name "Net-(OK2A-A)") (class "Default")
      (node (ref "OK2") (pin "1") (pinfunction "A_1") (pintype "passive"))
      (node (ref "R5") (pin "2") (pinfunction "2_2") (pintype "passive"))
    )
    (net (code "43") (name "Net-(OK2B-A)") (class "Default")
      (node (ref "OK2") (pin "3") (pinfunction "A_3") (pintype "passive"))
      (node (ref "R10") (pin "2") (pinfunction "2_2") (pintype "passive"))
    )
    (net (code "44") (name "Net-(Q1-G)") (class "Default")
      (node (ref "Q1") (pin "1") (pinfunction "G_1") (pintype "passive"))
      (node (ref "R17") (pin "2") (pinfunction "2_2") (pintype "passive"))
    )
    (net (code "45") (name "Net-(Q2-G)") (class "Default")
      (node (ref "Q2") (pin "1") (pinfunction "G_1") (pintype "passive"))
      (node (ref "R20") (pin "2") (pinfunction "2_2") (pintype "passive"))
    )
    (net (code "46") (name "Net-(Q3-G)") (class "Default")
      (node (ref "Q3") (pin "1") (pinfunction "G_1") (pintype "passive"))
      (node (ref "R24") (pin "2") (pinfunction "2_2") (pintype "passive"))
    )
    (net (code "47") (name "Net-(Q4-G)") (class "Default")
      (node (ref "Q4") (pin "3") (pinfunction "G_3") (pintype "passive"))
      (node (ref "R25") (pin "2") (pinfunction "2_2") (pintype "passive"))
    )
    (net (code "48") (name "Net-(Q5-G)") (class "Default")
      (node (ref "Q5") (pin "4") (pinfunction "G_4") (pintype "passive"))
      (node (ref "R26") (pin "2") (pinfunction "2_2") (pintype "passive"))
    )
    (net (code "49") (name "Net-(U1-REGOUT)") (class "Default")
      (node (ref "C3") (pin "1") (pinfunction "1_1") (pintype "passive"))
      (node (ref "U1") (pin "10") (pinfunction "REGOUT_10") (pintype "bidirectional"))
    )
    (net (code "50") (name "Net-(X3E-KL)") (class "Default")
      (node (ref "R14") (pin "2") (pinfunction "2_2") (pintype "passive"))
      (node (ref "X3") (pin "4") (pinfunction "KL_4") (pintype "passive"))
    )
    (net (code "51") (name "Net-(X4E-KL)") (class "Default")
      (node (ref "R15") (pin "2") (pinfunction "2_2") (pintype "passive"))
      (node (ref "X4") (pin "4") (pinfunction "KL_4") (pintype "passive"))
    )
    (net (code "52") (name "Net-(X6A-S)") (class "Default")
      (node (ref "Q5") (pin "5") (pinfunction "D_5") (pintype "passive"))
      (node (ref "Q5") (pin "6") (pinfunction "D_6") (pintype "passive"))
      (node (ref "Q5") (pin "7") (pinfunction "D_7") (pintype "passive"))
      (node (ref "Q5") (pin "8") (pinfunction "D_8") (pintype "passive"))
      (node (ref "X6") (pin "1") (pinfunction "S_1") (pintype "passive"))
    )
    (net (code "53") (name "R+12V") (class "Default")
      (node (ref "R13") (pin "2") (pinfunction "2_2") (pintype "passive"))
      (node (ref "R7") (pin "2") (pinfunction "2_2") (pintype "passive"))
      (node (ref "X4") (pin "1") (pinfunction "KL_1") (pintype "passive"))
      (node (ref "X4") (pin "2") (pinfunction "KL_2") (pintype "passive"))
      (node (ref "X4") (pin "5") (pinfunction "KL_5") (pintype "passive"))
      (node (ref "X4") (pin "7") (pinfunction "KL_7") (pintype "passive"))
    )
    (net (code "54") (name "RALI") (class "Default")
      (node (ref "OK2") (pin "8") (pinfunction "COL_8") (pintype "passive"))
      (node (ref "R7") (pin "1") (pinfunction "1_1") (pintype "passive"))
      (node (ref "X4") (pin "6") (pinfunction "KL_6") (pintype "passive"))
    )
    (net (code "55") (name "RALI_CTRL") (class "Default")
      (node (ref "A1") (pin "25") (pinfunction "P$25_25") (pintype "bidirectional"))
      (node (ref "R5") (pin "1") (pinfunction "1_1") (pintype "passive"))
    )
    (net (code "56") (name "RBLI") (class "Default")
      (node (ref "OK2") (pin "6") (pinfunction "COL_6") (pintype "passive"))
      (node (ref "R13") (pin "1") (pinfunction "1_1") (pintype "passive"))
      (node (ref "X4") (pin "8") (pinfunction "KL_8") (pintype "passive"))
    )
    (net (code "57") (name "RBLI_CTRL") (class "Default")
      (node (ref "A1") (pin "26") (pinfunction "P$26_26") (pintype "bidirectional"))
      (node (ref "R10") (pin "1") (pinfunction "1_1") (pintype "passive"))
    )
    (net (code "58") (name "RD_N") (class "Default")
      (node (ref "A1") (pin "36") (pinfunction "P$36_36") (pintype "bidirectional"))
      (node (ref "X7") (pin "6") (pinfunction "RD-_6") (pintype "passive"))
    )
    (net (code "59") (name "RD_P") (class "Default")
      (node (ref "A1") (pin "35") (pinfunction "P$35_35") (pintype "bidirectional"))
      (node (ref "X7") (pin "4") (pinfunction "RD+_4") (pintype "passive"))
    )
    (net (code "60") (name "REA") (class "Default")
      (node (ref "U2") (pin "13") (pinfunction "B1_13") (pintype "bidirectional"))
      (node (ref "X2") (pin "3") (pinfunction "S_3") (pintype "passive"))
    )
    (net (code "61") (name "REA3") (class "Default")
      (node (ref "A1") (pin "30") (pinfunction "P$30_30") (pintype "bidirectional"))
      (node (ref "U2") (pin "2") (pinfunction "A1_2") (pintype "bidirectional"))
    )
    (net (code "62") (name "REB") (class "Default")
      (node (ref "U2") (pin "12") (pinfunction "B2_12") (pintype "bidirectional"))
      (node (ref "X2") (pin "5") (pinfunction "S_5") (pintype "passive"))
    )
    (net (code "63") (name "REB3") (class "Default")
      (node (ref "A1") (pin "29") (pinfunction "P$29_29") (pintype "bidirectional"))
      (node (ref "U2") (pin "3") (pinfunction "A2_3") (pintype "bidirectional"))
    )
    (net (code "64") (name "RED") (class "Default")
      (node (ref "R17") (pin "1") (pinfunction "1_1") (pintype "passive"))
      (node (ref "U3") (pin "16") (pinfunction "B1_16") (pintype "bidirectional"))
    )
    (net (code "65") (name "RED_3V3") (class "Default")
      (node (ref "A1") (pin "12") (pinfunction "P$12_12") (pintype "bidirectional"))
      (node (ref "U3") (pin "1") (pinfunction "A1_1") (pintype "bidirectional"))
    )
    (net (code "66") (name "RED_OUT") (class "Default")
      (node (ref "J1") (pin "3") (pinfunction "3_3") (pintype "passive"))
      (node (ref "Q1") (pin "3") (pinfunction "D_3") (pintype "passive"))
    )
    (net (code "67") (name "RGND") (class "Default")
      (node (ref "OK2") (pin "5") (pinfunction "EMIT_5") (pintype "passive"))
      (node (ref "OK2") (pin "7") (pinfunction "EMIT_7") (pintype "passive"))
      (node (ref "R15") (pin "1") (pinfunction "1_1") (pintype "passive"))
      (node (ref "X4") (pin "10") (pinfunction "KL_10") (pintype "passive"))
      (node (ref "X4") (pin "9") (pinfunction "KL_9") (pintype "passive"))
    )
    (net (code "68") (name "SAFETY_LIGHT") (class "Default")
      (node (ref "R25") (pin "1") (pinfunction "1_1") (pintype "passive"))
      (node (ref "U3") (pin "11") (pinfunction "B5_11") (pintype "bidirectional"))
    )
    (net (code "69") (name "SAFETY_LIGHT_3V3") (class "Default")
      (node (ref "A1") (pin "19") (pinfunction "P$19_19") (pintype "bidirectional"))
      (node (ref "U3") (pin "6") (pinfunction "A5_6") (pintype "bidirectional"))
    )
    (net (code "70") (name "SCL") (class "Default")
      (node (ref "A1") (pin "10") (pinfunction "P$10_10") (pintype "bidirectional"))
      (node (ref "R8") (pin "1") (pinfunction "1_1") (pintype "passive"))
      (node (ref "U1") (pin "23") (pinfunction "SCL/SCLK_23") (pintype "bidirectional"))
    )
    (net (code "71") (name "SDA") (class "Default")
      (node (ref "A1") (pin "9") (pinfunction "P$9_9") (pintype "bidirectional"))
      (node (ref "R11") (pin "1") (pinfunction "1_1") (pintype "passive"))
      (node (ref "U1") (pin "24") (pinfunction "SDA/SDI_24") (pintype "bidirectional"))
    )
    (net (code "72") (name "TD_N") (class "Default")
      (node (ref "A1") (pin "34") (pinfunction "P$34_34") (pintype "bidirectional"))
      (node (ref "X7") (pin "3") (pinfunction "TD-_3") (pintype "passive"))
    )
    (net (code "73") (name "TD_P") (class "Default")
      (node (ref "A1") (pin "33") (pinfunction "P$33_33") (pintype "bidirectional"))
      (node (ref "X7") (pin "1") (pinfunction "TD+_1") (pintype "passive"))
    )
    (net (code "74") (name "unconnected-(A1-P$3-Pad3)") (class "Default")
      (node (ref "A1") (pin "3") (pinfunction "P$3_3") (pintype "bidirectional"))
    )
    (net (code "75") (name "unconnected-(A1-P$4-Pad4)") (class "Default")
      (node (ref "A1") (pin "4") (pinfunction "P$4_4") (pintype "bidirectional"))
    )
    (net (code "76") (name "unconnected-(A1-P$5-Pad5)") (class "Default")
      (node (ref "A1") (pin "5") (pinfunction "P$5_5") (pintype "bidirectional"))
    )
    (net (code "77") (name "unconnected-(A1-P$6-Pad6)") (class "Default")
      (node (ref "A1") (pin "6") (pinfunction "P$6_6") (pintype "bidirectional"))
    )
    (net (code "78") (name "unconnected-(A1-P$7-Pad7)") (class "Default")
      (node (ref "A1") (pin "7") (pinfunction "P$7_7") (pintype "bidirectional"))
    )
    (net (code "79") (name "unconnected-(A1-P$16-Pad16)") (class "Default")
      (node (ref "A1") (pin "16") (pinfunction "P$16_16") (pintype "bidirectional"))
    )
    (net (code "80") (name "unconnected-(A1-P$17-Pad17)") (class "Default")
      (node (ref "A1") (pin "17") (pinfunction "P$17_17") (pintype "bidirectional"))
    )
    (net (code "81") (name "unconnected-(A1-P$37-Pad37)") (class "Default")
      (node (ref "A1") (pin "37") (pinfunction "P$37_37") (pintype "bidirectional"))
    )
    (net (code "82") (name "unconnected-(A1-P$38-Pad38)") (class "Default")
      (node (ref "A1") (pin "38") (pinfunction "P$38_38") (pintype "bidirectional"))
    )
    (net (code "83") (name "unconnected-(J1-Pad7)") (class "Default")
      (node (ref "J1") (pin "7") (pinfunction "7_7") (pintype "passive"))
    )
    (net (code "84") (name "unconnected-(J1-Pad8)") (class "Default")
      (node (ref "J1") (pin "8") (pinfunction "8_8") (pintype "passive"))
    )
    (net (code "85") (name "unconnected-(J1-Pad9)") (class "Default")
      (node (ref "J1") (pin "9") (pinfunction "9_9") (pintype "passive"))
    )
    (net (code "86") (name "unconnected-(U1-AUX_CL-Pad7)") (class "Default")
      (node (ref "U1") (pin "7") (pinfunction "AUX_CL_7") (pintype "bidirectional"))
    )
    (net (code "87") (name "unconnected-(U1-AUX_DA-Pad21)") (class "Default")
      (node (ref "U1") (pin "21") (pinfunction "AUX_DA_21") (pintype "bidirectional"))
    )
    (net (code "88") (name "unconnected-(U2-NC-Pad9)") (class "Default")
      (node (ref "U2") (pin "9") (pinfunction "NC_9") (pintype "passive"))
    )
    (net (code "89") (name "unconnected-(U2-NC_2-Pad6)") (class "Default")
      (node (ref "U2") (pin "6") (pinfunction "NC_2_6") (pintype "passive"))
    )
    (net (code "90") (name "unconnected-(U3-A6-Pad7)") (class "Default")
      (node (ref "U3") (pin "7") (pinfunction "A6_7") (pintype "bidirectional"))
    )
    (net (code "91") (name "unconnected-(U3-B6-Pad10)") (class "Default")
      (node (ref "U3") (pin "10") (pinfunction "B6_10") (pintype "bidirectional"))
    )
    (net (code "92") (name "unconnected-(X1-Pad4)") (class "Default")
      (node (ref "X1") (pin "4") (pinfunction "4_4") (pintype "passive"))
    )
    (net (code "93") (name "unconnected-(X2B-S-Pad2)") (class "Default")
      (node (ref "X2") (pin "2") (pinfunction "S_2") (pintype "passive"))
    )
    (net (code "94") (name "unconnected-(X3D-KL-Pad3)") (class "Default")
      (node (ref "X3") (pin "3") (pinfunction "KL_3") (pintype "passive"))
    )
    (net (code "95") (name "unconnected-(X4D-KL-Pad3)") (class "Default")
      (node (ref "X4") (pin "3") (pinfunction "KL_3") (pintype "passive"))
    )
    (net (code "96") (name "unconnected-(X5B-S-Pad2)") (class "Default")
      (node (ref "X5") (pin "2") (pinfunction "S_2") (pintype "passive"))
    )
    (net (code "97") (name "unconnected-(X7-C_GND-Pad8)") (class "Default")
      (node (ref "X7") (pin "8") (pinfunction "C_GND_8") (pintype "passive"))
    )
    (net (code "98") (name "unconnected-(X7-NC-Pad7)") (class "Default")
      (node (ref "X7") (pin "7") (pinfunction "NC_7") (pintype "passive"))
    )
  )
)
